# final.net
KiCad netlist of a schematic drawn in EAGLE
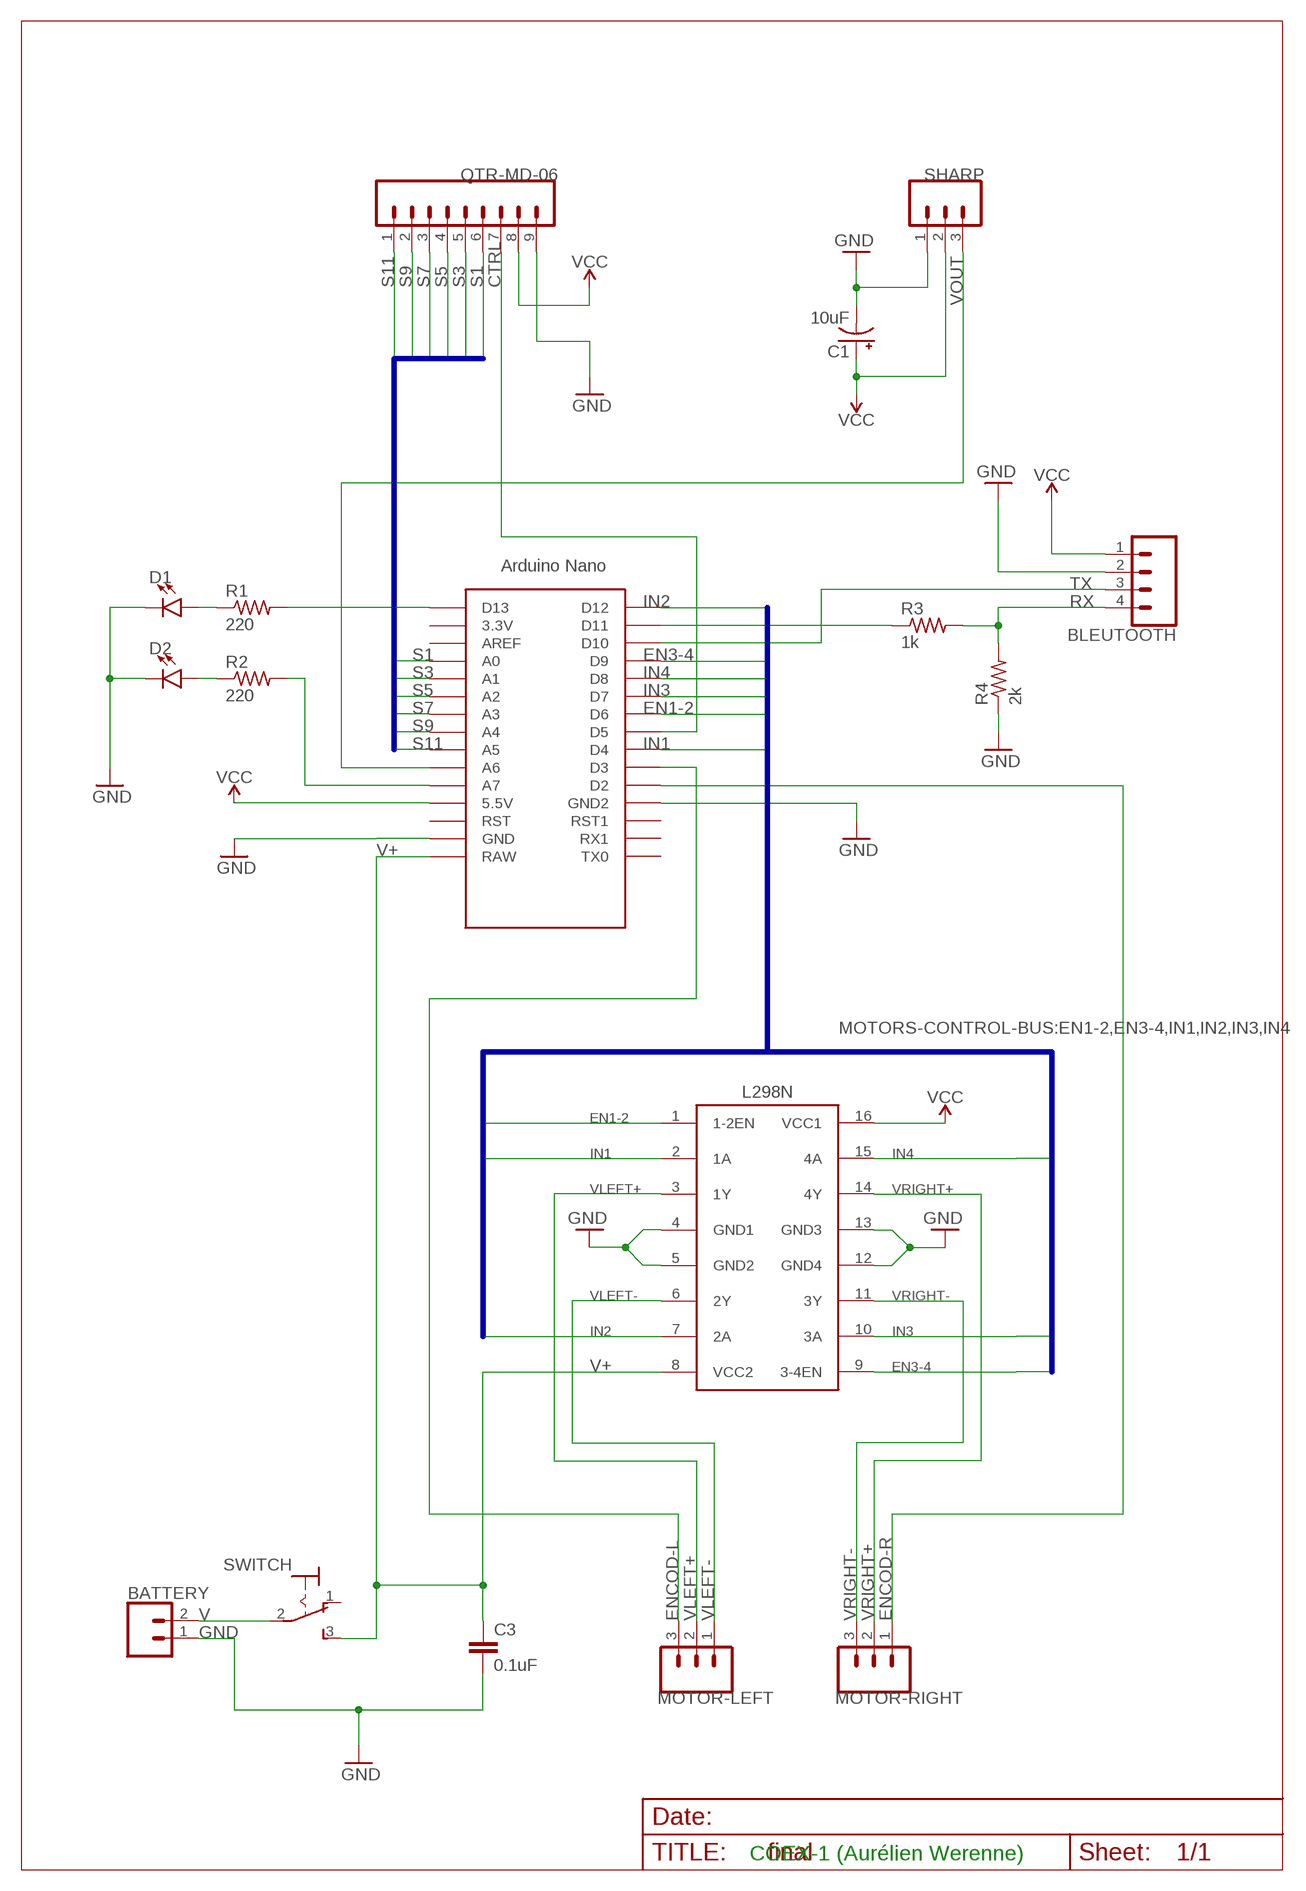
[diagram p0: schematic, sheet 1]

(export (version "E")
  (design (tool "Eeschema 10.0.6"))
  (components
    (comp (ref "BATTERY")
      (value "CONN_02")
      (footprint "eagle-import:1X02")
      (libsource (lib "eagle-import") (part "CONN_02"))
    )
    (comp (ref "BLEUTOOTH")
      (value "CONN_04")
      (footprint "eagle-import:1X04")
      (libsource (lib "eagle-import") (part "CONN_04"))
    )
    (comp (ref "C1")
      (value "10uF")
      (footprint "eagle-import:CPOL-RADIAL-2.5MM-5MM")
      (libsource (lib "eagle-import") (part "10UF-POLAR-RADIAL-2.5MM-25V-20%"))
    )
    (comp (ref "C3")
      (value "0.1uF")
      (footprint "eagle-import:CAP-PTH-SMALL-KIT")
      (libsource (lib "eagle-import") (part "0.1UF-KIT-EZ-50V-20%"))
    )
    (comp (ref "D1")
      (value "LED3MM")
      (footprint "eagle-import:LED_3MM")
      (libsource (lib "eagle-import") (part "LED3MM"))
    )
    (comp (ref "D2")
      (value "LED3MM")
      (footprint "eagle-import:LED_3MM")
      (libsource (lib "eagle-import") (part "LED3MM"))
    )
    (comp (ref "L298N")
      (value "L293D")
      (footprint "eagle-import:DIL16")
      (libsource (lib "eagle-import") (part "L293D"))
    )
    (comp (ref "MOTOR-LEFT")
      (value "CONN_03")
      (footprint "eagle-import:1X03")
      (libsource (lib "eagle-import") (part "CONN_03"))
    )
    (comp (ref "MOTOR-RIGHT")
      (value "CONN_03")
      (footprint "eagle-import:1X03")
      (libsource (lib "eagle-import") (part "CONN_03"))
    )
    (comp (ref "QTR-MD-06")
      (value "CONN_09")
      (footprint "eagle-import:1X09")
      (libsource (lib "eagle-import") (part "CONN_09"))
    )
    (comp (ref "R1")
      (value "220")
      (footprint "eagle-import:0207_12")
      (libsource (lib "eagle-import") (part "R-US_0207/12"))
    )
    (comp (ref "R2")
      (value "220")
      (footprint "eagle-import:0207_12")
      (libsource (lib "eagle-import") (part "R-US_0207/12"))
    )
    (comp (ref "R3")
      (value "1k")
      (footprint "eagle-import:0207_12")
      (libsource (lib "eagle-import") (part "R-US_0207/12"))
    )
    (comp (ref "R4")
      (value "2k")
      (footprint "eagle-import:0207_12")
      (libsource (lib "eagle-import") (part "R-US_0207/12"))
    )
    (comp (ref "SHARP")
      (value "CONN_03")
      (footprint "eagle-import:1X03")
      (libsource (lib "eagle-import") (part "CONN_03"))
    )
    (comp (ref "SWITCH")
      (value "320-916")
      (footprint "eagle-import:320-916")
      (libsource (lib "eagle-import") (part "320-916"))
    )
    (comp (ref "U$1")
      (value "NANO")
      (footprint "eagle-import:NANO")
      (libsource (lib "eagle-import") (part "NANO"))
    )
  )
  (nets
    (net (code "2") (name "/CTRL") (class "Default")
      (node (ref "QTR-MD-06") (pin "7") (pinfunction "7_7") (pintype "passive"))
      (node (ref "U$1") (pin "D5") (pinfunction "D5_D5") (pintype "bidirectional"))
    )
    (net (code "3") (name "/EN1-2") (class "Default")
      (node (ref "L298N") (pin "1") (pinfunction "1-2EN_1") (pintype "input"))
      (node (ref "U$1") (pin "D6") (pinfunction "D6_D6") (pintype "bidirectional"))
    )
    (net (code "4") (name "/EN3-4") (class "Default")
      (node (ref "L298N") (pin "9") (pinfunction "3-4EN_9") (pintype "input"))
      (node (ref "U$1") (pin "D9") (pinfunction "D9_D9") (pintype "bidirectional"))
    )
    (net (code "5") (name "/ENCOD-L") (class "Default")
      (node (ref "MOTOR-LEFT") (pin "3") (pinfunction "3_3") (pintype "passive"))
      (node (ref "U$1") (pin "D3") (pinfunction "D3_D3") (pintype "bidirectional"))
    )
    (net (code "6") (name "/ENCOD-R") (class "Default")
      (node (ref "MOTOR-RIGHT") (pin "1") (pinfunction "1_1") (pintype "passive"))
      (node (ref "U$1") (pin "D2") (pinfunction "D2_D2") (pintype "bidirectional"))
    )
    (net (code "7") (name "/IN1") (class "Default")
      (node (ref "L298N") (pin "2") (pinfunction "1A_2") (pintype "input"))
      (node (ref "U$1") (pin "D4") (pinfunction "D4_D4") (pintype "bidirectional"))
    )
    (net (code "8") (name "/IN2") (class "Default")
      (node (ref "L298N") (pin "7") (pinfunction "2A_7") (pintype "input"))
      (node (ref "U$1") (pin "D12") (pinfunction "D12_D12") (pintype "bidirectional"))
    )
    (net (code "9") (name "/IN3") (class "Default")
      (node (ref "L298N") (pin "10") (pinfunction "3A_10") (pintype "input"))
      (node (ref "U$1") (pin "D7") (pinfunction "D7_D7") (pintype "bidirectional"))
    )
    (net (code "10") (name "/IN4") (class "Default")
      (node (ref "L298N") (pin "15") (pinfunction "4A_15") (pintype "input"))
      (node (ref "U$1") (pin "D8") (pinfunction "D8_D8") (pintype "bidirectional"))
    )
    (net (code "11") (name "/RX") (class "Default")
      (node (ref "BLEUTOOTH") (pin "4") (pinfunction "4_4") (pintype "passive"))
      (node (ref "R3") (pin "2") (pinfunction "2_2") (pintype "passive"))
      (node (ref "R4") (pin "2") (pinfunction "2_2") (pintype "passive"))
    )
    (net (code "12") (name "/S1") (class "Default")
      (node (ref "QTR-MD-06") (pin "6") (pinfunction "6_6") (pintype "passive"))
      (node (ref "U$1") (pin "A0") (pinfunction "A0_A0") (pintype "bidirectional"))
    )
    (net (code "13") (name "/S3") (class "Default")
      (node (ref "QTR-MD-06") (pin "5") (pinfunction "5_5") (pintype "passive"))
      (node (ref "U$1") (pin "A1") (pinfunction "A1_A1") (pintype "bidirectional"))
    )
    (net (code "14") (name "/S5") (class "Default")
      (node (ref "QTR-MD-06") (pin "4") (pinfunction "4_4") (pintype "passive"))
      (node (ref "U$1") (pin "A2") (pinfunction "A2_A2") (pintype "bidirectional"))
    )
    (net (code "15") (name "/S7") (class "Default")
      (node (ref "QTR-MD-06") (pin "3") (pinfunction "3_3") (pintype "passive"))
      (node (ref "U$1") (pin "A3") (pinfunction "A3_A3") (pintype "bidirectional"))
    )
    (net (code "16") (name "/S9") (class "Default")
      (node (ref "QTR-MD-06") (pin "2") (pinfunction "2_2") (pintype "passive"))
      (node (ref "U$1") (pin "A4") (pinfunction "A4_A4") (pintype "bidirectional"))
    )
    (net (code "17") (name "/S11") (class "Default")
      (node (ref "QTR-MD-06") (pin "1") (pinfunction "1_1") (pintype "passive"))
      (node (ref "U$1") (pin "A5") (pinfunction "A5_A5") (pintype "bidirectional"))
    )
    (net (code "18") (name "/TX") (class "Default")
      (node (ref "BLEUTOOTH") (pin "3") (pinfunction "3_3") (pintype "passive"))
      (node (ref "U$1") (pin "D10") (pinfunction "D10_D10") (pintype "bidirectional"))
    )
    (net (code "19") (name "/V") (class "Default")
      (node (ref "BATTERY") (pin "2") (pinfunction "2_2") (pintype "passive"))
      (node (ref "SWITCH") (pin "2") (pinfunction "P_2") (pintype "passive"))
    )
    (net (code "20") (name "/V+") (class "Default")
      (node (ref "C3") (pin "1") (pinfunction "1_1") (pintype "passive"))
      (node (ref "L298N") (pin "8") (pinfunction "VCC2_8") (pintype "power_in"))
      (node (ref "SWITCH") (pin "3") (pinfunction "S_3") (pintype "passive"))
      (node (ref "U$1") (pin "RAW") (pinfunction "RAW_RAW") (pintype "bidirectional"))
    )
    (net (code "21") (name "/VLEFT+") (class "Default")
      (node (ref "L298N") (pin "3") (pinfunction "1Y_3") (pintype "output"))
      (node (ref "MOTOR-LEFT") (pin "2") (pinfunction "2_2") (pintype "passive"))
    )
    (net (code "22") (name "/VLEFT-") (class "Default")
      (node (ref "L298N") (pin "6") (pinfunction "2Y_6") (pintype "output"))
      (node (ref "MOTOR-LEFT") (pin "1") (pinfunction "1_1") (pintype "passive"))
    )
    (net (code "23") (name "/VOUT") (class "Default")
      (node (ref "SHARP") (pin "3") (pinfunction "3_3") (pintype "passive"))
      (node (ref "U$1") (pin "A6") (pinfunction "A6_A6") (pintype "bidirectional"))
    )
    (net (code "24") (name "/VRIGHT+") (class "Default")
      (node (ref "L298N") (pin "14") (pinfunction "4Y_14") (pintype "output"))
      (node (ref "MOTOR-RIGHT") (pin "2") (pinfunction "2_2") (pintype "passive"))
    )
    (net (code "25") (name "/VRIGHT-") (class "Default")
      (node (ref "L298N") (pin "11") (pinfunction "3Y_11") (pintype "output"))
      (node (ref "MOTOR-RIGHT") (pin "3") (pinfunction "3_3") (pintype "passive"))
    )
    (net (code "27") (name "GND") (class "Default")
      (node (ref "BATTERY") (pin "1") (pinfunction "1_1") (pintype "passive"))
      (node (ref "BLEUTOOTH") (pin "2") (pinfunction "2_2") (pintype "passive"))
      (node (ref "C1") (pin "2") (pinfunction "-_2") (pintype "passive"))
      (node (ref "C3") (pin "2") (pinfunction "2_2") (pintype "passive"))
      (node (ref "D1") (pin "K") (pinfunction "C_K") (pintype "passive"))
      (node (ref "D2") (pin "K") (pinfunction "C_K") (pintype "passive"))
      (node (ref "L298N") (pin "12") (pinfunction "GND4_12") (pintype "power_in"))
      (node (ref "L298N") (pin "13") (pinfunction "GND3_13") (pintype "power_in"))
      (node (ref "L298N") (pin "4") (pinfunction "GND1_4") (pintype "power_in"))
      (node (ref "L298N") (pin "5") (pinfunction "GND2_5") (pintype "power_in"))
      (node (ref "QTR-MD-06") (pin "9") (pinfunction "9_9") (pintype "passive"))
      (node (ref "R4") (pin "1") (pinfunction "1_1") (pintype "passive"))
      (node (ref "SHARP") (pin "1") (pinfunction "1_1") (pintype "passive"))
      (node (ref "U$1") (pin "GND") (pinfunction "GND_GND") (pintype "bidirectional"))
      (node (ref "U$1") (pin "GND1") (pinfunction "GND2_GND1") (pintype "bidirectional"))
    )
    (net (code "28") (name "Net-(D1-PadA)") (class "Default")
      (node (ref "D1") (pin "A") (pinfunction "A_A") (pintype "passive"))
      (node (ref "R1") (pin "1") (pinfunction "1_1") (pintype "passive"))
    )
    (net (code "29") (name "Net-(D2-PadA)") (class "Default")
      (node (ref "D2") (pin "A") (pinfunction "A_A") (pintype "passive"))
      (node (ref "R2") (pin "1") (pinfunction "1_1") (pintype "passive"))
    )
    (net (code "30") (name "Net-(R1-Pad2)") (class "Default")
      (node (ref "R1") (pin "2") (pinfunction "2_2") (pintype "passive"))
      (node (ref "U$1") (pin "D13") (pinfunction "D13_D13") (pintype "bidirectional"))
    )
    (net (code "31") (name "Net-(R2-Pad2)") (class "Default")
      (node (ref "R2") (pin "2") (pinfunction "2_2") (pintype "passive"))
      (node (ref "U$1") (pin "A7") (pinfunction "A7_A7") (pintype "bidirectional"))
    )
    (net (code "32") (name "Net-(R3-Pad1)") (class "Default")
      (node (ref "R3") (pin "1") (pinfunction "1_1") (pintype "passive"))
      (node (ref "U$1") (pin "D11") (pinfunction "D11_D11") (pintype "bidirectional"))
    )
    (net (code "33") (name "VCC") (class "Default")
      (node (ref "BLEUTOOTH") (pin "1") (pinfunction "1_1") (pintype "passive"))
      (node (ref "C1") (pin "1") (pinfunction "+_1") (pintype "passive"))
      (node (ref "L298N") (pin "16") (pinfunction "VCC1_16") (pintype "power_in"))
      (node (ref "QTR-MD-06") (pin "8") (pinfunction "8_8") (pintype "passive"))
      (node (ref "SHARP") (pin "2") (pinfunction "2_2") (pintype "passive"))
      (node (ref "U$1") (pin "5V") (pinfunction "5.5V_5V") (pintype "bidirectional"))
    )
    (net (code "34") (name "unconnected-(SWITCH-O-Pad1)") (class "Default")
      (node (ref "SWITCH") (pin "1") (pinfunction "O_1") (pintype "passive"))
    )
    (net (code "35") (name "unconnected-(U$1-Pad3.3V)") (class "Default")
      (node (ref "U$1") (pin "3.3V") (pinfunction "3.3V_3.3V") (pintype "bidirectional"))
    )
    (net (code "36") (name "unconnected-(U$1-PadAREF)") (class "Default")
      (node (ref "U$1") (pin "AREF") (pinfunction "AREF_AREF") (pintype "bidirectional"))
    )
    (net (code "37") (name "unconnected-(U$1-PadICSP1)") (class "Default")
      (node (ref "U$1") (pin "ICSP1") (pinfunction "ICSP1_ICSP1") (pintype "bidirectional"))
    )
    (net (code "38") (name "unconnected-(U$1-PadICSP2)") (class "Default")
      (node (ref "U$1") (pin "ICSP2") (pinfunction "ICSP2_ICSP2") (pintype "bidirectional"))
    )
    (net (code "39") (name "unconnected-(U$1-PadICSP3)") (class "Default")
      (node (ref "U$1") (pin "ICSP3") (pinfunction "ICSP3_ICSP3") (pintype "bidirectional"))
    )
    (net (code "40") (name "unconnected-(U$1-PadICSP4)") (class "Default")
      (node (ref "U$1") (pin "ICSP4") (pinfunction "ICSP4_ICSP4") (pintype "bidirectional"))
    )
    (net (code "41") (name "unconnected-(U$1-PadICSP5)") (class "Default")
      (node (ref "U$1") (pin "ICSP5") (pinfunction "ICSP5_ICSP5") (pintype "bidirectional"))
    )
    (net (code "42") (name "unconnected-(U$1-PadICSP6)") (class "Default")
      (node (ref "U$1") (pin "ICSP6") (pinfunction "ICSP6_ICSP6") (pintype "bidirectional"))
    )
    (net (code "43") (name "unconnected-(U$1-PadRST)") (class "Default")
      (node (ref "U$1") (pin "RST") (pinfunction "RST_RST") (pintype "bidirectional"))
    )
    (net (code "44") (name "unconnected-(U$1-PadRST1)") (class "Default")
      (node (ref "U$1") (pin "RST1") (pinfunction "RST1_RST1") (pintype "bidirectional"))
    )
    (net (code "45") (name "unconnected-(U$1-PadRX1)") (class "Default")
      (node (ref "U$1") (pin "RX1") (pinfunction "RX1_RX1") (pintype "bidirectional"))
    )
    (net (code "46") (name "unconnected-(U$1-PadTX0)") (class "Default")
      (node (ref "U$1") (pin "TX0") (pinfunction "TX0_TX0") (pintype "bidirectional"))
    )
  )
)
